# p03_display.net
KiCad netlist of a schematic drawn in Altium Designer
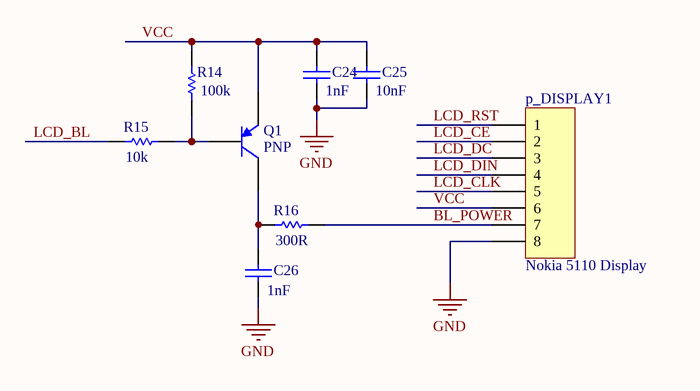
[diagram p0: p03_display.SchDoc]

(export (version "E")
  (design (tool "Eeschema 10.0.6"))
  (components
    (comp (ref "C24")
      (value "1nF")
      (footprint "Miscellaneous Devices:C0805")
      (description "Capacitor")
      (fields (field (name "Comment") "Cap") (field (name "PUBLISHER") "Altium Limited"))
      (libsource (lib "Miscellaneous Devices") (part "Cap"))
    )
    (comp (ref "C25")
      (value "10nF")
      (footprint "Miscellaneous Devices:C0805")
      (description "Capacitor")
      (fields (field (name "Comment") "Cap") (field (name "PUBLISHER") "Altium Limited"))
      (libsource (lib "Miscellaneous Devices") (part "Cap"))
    )
    (comp (ref "C26")
      (value "1nF")
      (footprint "Miscellaneous Devices:C0805")
      (description "Capacitor")
      (fields (field (name "Comment") "Cap") (field (name "PUBLISHER") "Altium Limited"))
      (libsource (lib "Miscellaneous Devices") (part "Cap"))
    )
    (comp (ref "p_DISPLAY1")
      (value "Nokia 5110 Display")
      (footprint "HDR1X8")
      (description "Header, 8-Pin")
      (fields (field (name "PUBLISHER") "Altium Limited"))
      (libsource (lib "Miscellaneous Connectors") (part "Header 8"))
    )
    (comp (ref "Q1")
      (value "PNP")
      (footprint "SOT-23B_N")
      (description "PNP Bipolar Transistor")
      (fields (field (name "PUBLISHER") "Altium Limited"))
      (libsource (lib "Miscellaneous Devices") (part "PNP"))
    )
    (comp (ref "R14")
      (value "100k")
      (footprint "6-0805_M")
      (description "Resistor")
      (fields (field (name "Comment") "Res1") (field (name "PUBLISHER") "Altium Limited"))
      (libsource (lib "Miscellaneous Devices") (part "Res1"))
    )
    (comp (ref "R15")
      (value "10k")
      (footprint "6-0805_M")
      (description "Resistor")
      (fields (field (name "Comment") "Res1") (field (name "PUBLISHER") "Altium Limited"))
      (libsource (lib "Miscellaneous Devices") (part "Res1"))
    )
    (comp (ref "R16")
      (value "300R")
      (footprint "6-0805_M")
      (description "Resistor")
      (fields (field (name "Comment") "Res1") (field (name "PUBLISHER") "Altium Limited"))
      (libsource (lib "Miscellaneous Devices") (part "Res1"))
    )
  )
  (nets
    (net (code "1") (name "/BL_POWER") (class "Default")
      (node (ref "R16") (pin "1") (pinfunction "1_1") (pintype "passive"))
      (node (ref "p_DISPLAY1") (pin "7") (pinfunction "7_7") (pintype "passive"))
    )
    (net (code "2") (name "/LCD_BL") (class "Default")
      (node (ref "R15") (pin "2") (pinfunction "2_2") (pintype "passive"))
    )
    (net (code "3") (name "/LCD_CE") (class "Default")
      (node (ref "p_DISPLAY1") (pin "2") (pinfunction "2_2") (pintype "passive"))
    )
    (net (code "4") (name "/LCD_CLK") (class "Default")
      (node (ref "p_DISPLAY1") (pin "5") (pinfunction "5_5") (pintype "passive"))
    )
    (net (code "5") (name "/LCD_DC") (class "Default")
      (node (ref "p_DISPLAY1") (pin "3") (pinfunction "3_3") (pintype "passive"))
    )
    (net (code "6") (name "/LCD_DIN") (class "Default")
      (node (ref "p_DISPLAY1") (pin "4") (pinfunction "4_4") (pintype "passive"))
    )
    (net (code "7") (name "/LCD_RST") (class "Default")
      (node (ref "p_DISPLAY1") (pin "1") (pinfunction "1_1") (pintype "passive"))
    )
    (net (code "8") (name "/VCC") (class "Default")
      (node (ref "C24") (pin "2") (pinfunction "2_2") (pintype "passive"))
      (node (ref "C25") (pin "2") (pinfunction "2_2") (pintype "passive"))
      (node (ref "Q1") (pin "3") (pinfunction "E_3") (pintype "passive"))
      (node (ref "R14") (pin "1") (pinfunction "1_1") (pintype "passive"))
      (node (ref "p_DISPLAY1") (pin "6") (pinfunction "6_6") (pintype "passive"))
    )
    (net (code "9") (name "GND") (class "Default")
      (node (ref "C24") (pin "1") (pinfunction "1_1") (pintype "passive"))
      (node (ref "C25") (pin "1") (pinfunction "1_1") (pintype "passive"))
      (node (ref "C26") (pin "1") (pinfunction "1_1") (pintype "passive"))
      (node (ref "p_DISPLAY1") (pin "8") (pinfunction "8_8") (pintype "passive"))
    )
    (net (code "10") (name "Net-(Q1-B)") (class "Default")
      (node (ref "Q1") (pin "2") (pinfunction "B_2") (pintype "passive"))
      (node (ref "R14") (pin "2") (pinfunction "2_2") (pintype "passive"))
      (node (ref "R15") (pin "1") (pinfunction "1_1") (pintype "passive"))
    )
    (net (code "11") (name "Net-(Q1-C)") (class "Default")
      (node (ref "C26") (pin "2") (pinfunction "2_2") (pintype "passive"))
      (node (ref "Q1") (pin "1") (pinfunction "C_1") (pintype "passive"))
      (node (ref "R16") (pin "2") (pinfunction "2_2") (pintype "passive"))
    )
  )
)
